# RL78G10_ToF_A2.net
KiCad netlist of a schematic drawn in EAGLE
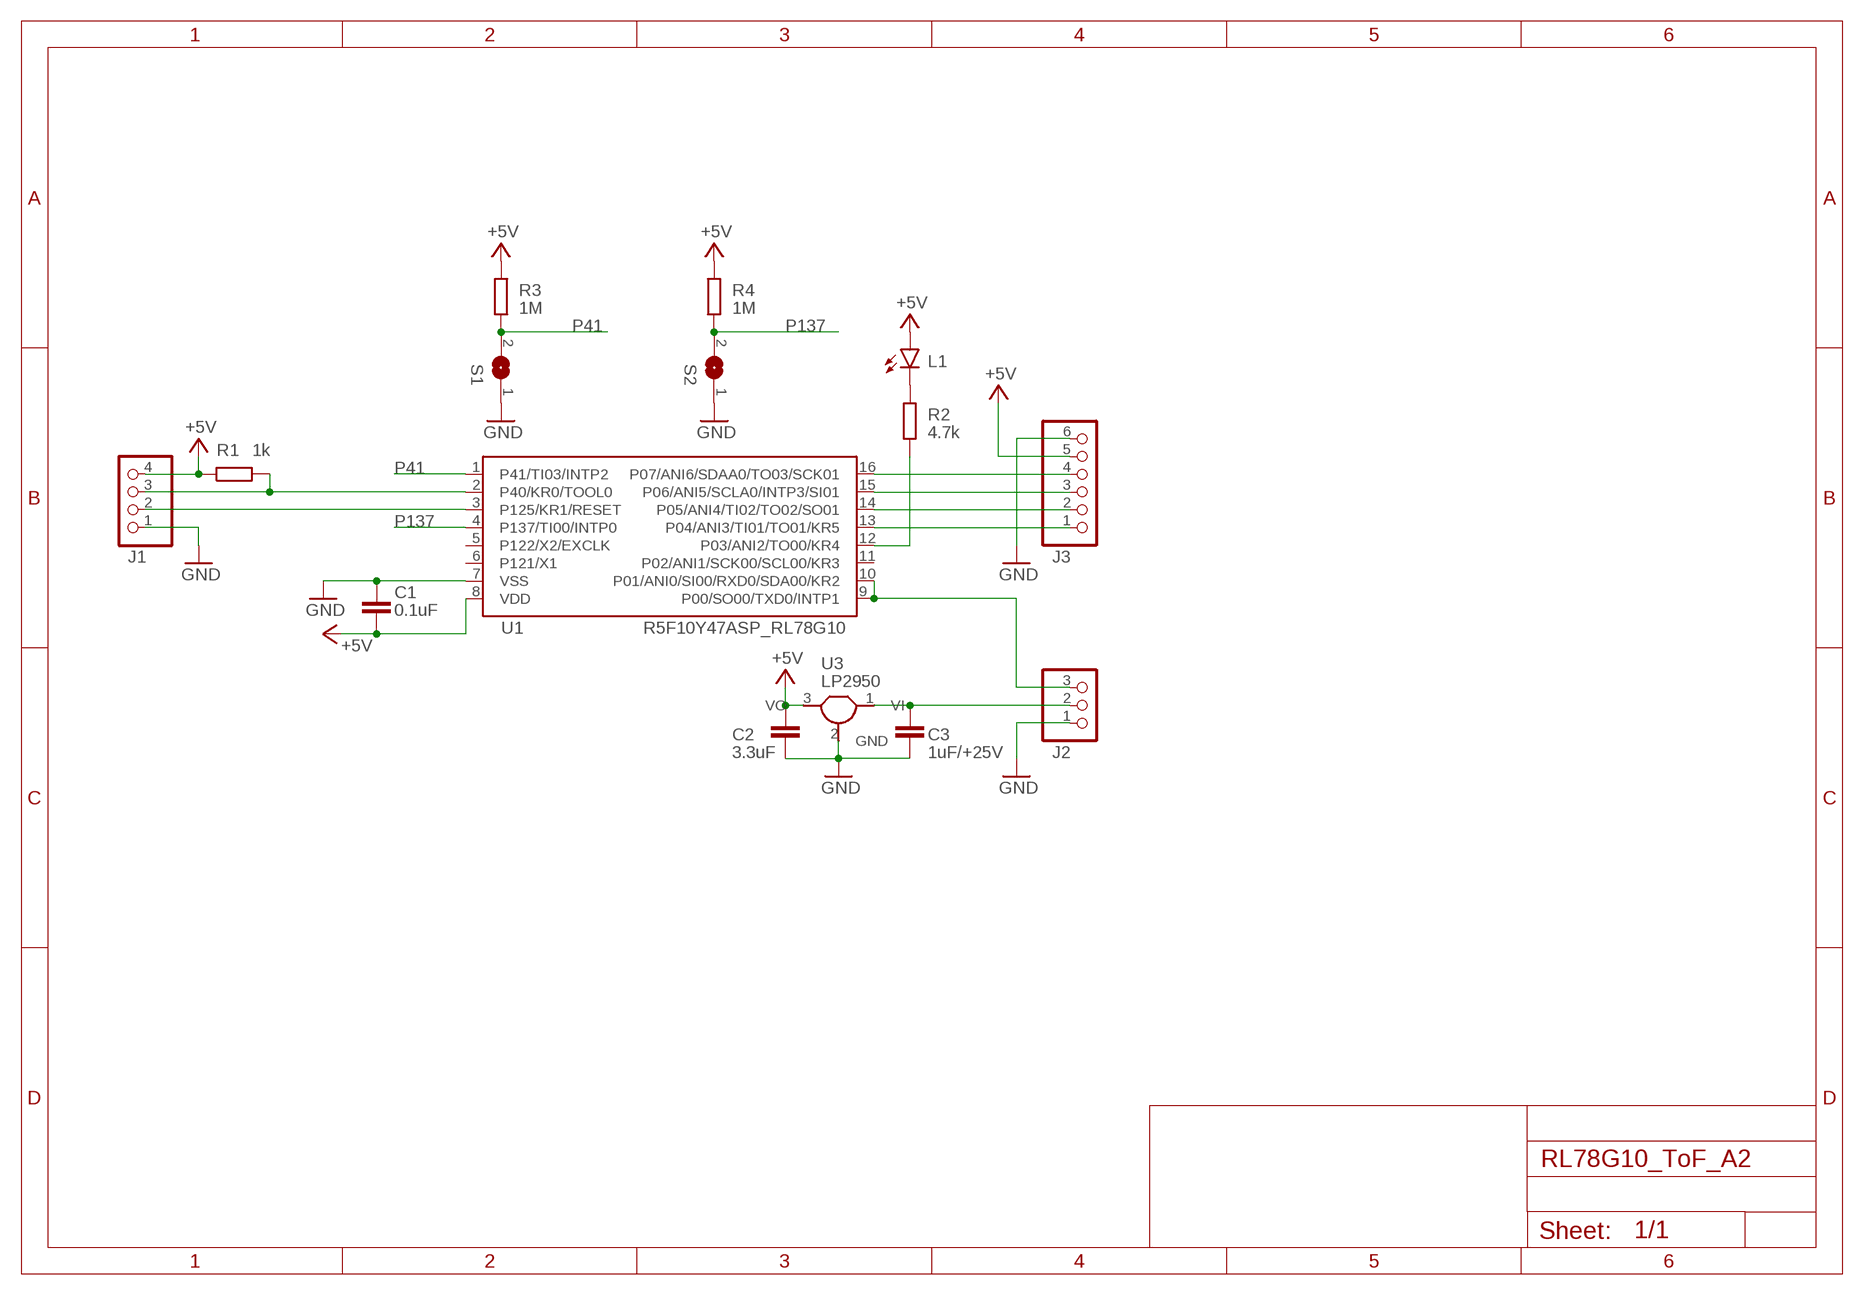
[diagram p0: schematic, sheet 1]

(export (version "E")
  (design (tool "Eeschema 10.0.6"))
  (components
    (comp (ref "C1")
      (value "0.1uF")
      (footprint "eagle-import:C0603")
      (libsource (lib "eagle-import") (part "C-EUC0603"))
    )
    (comp (ref "C2")
      (value "3.3uF")
      (footprint "eagle-import:C0805")
      (libsource (lib "eagle-import") (part "C-EUC0805"))
    )
    (comp (ref "C3")
      (value "1uF/+25V")
      (footprint "eagle-import:C0805")
      (libsource (lib "eagle-import") (part "C-EUC0805"))
    )
    (comp (ref "J1")
      (value "PINHD_1X4")
      (footprint "eagle-import:PINHD_1X04")
      (libsource (lib "eagle-import") (part "PINHD_1X4"))
    )
    (comp (ref "J2")
      (value "PINHD_1X3")
      (footprint "eagle-import:PINHD_1X03")
      (libsource (lib "eagle-import") (part "PINHD_1X3"))
    )
    (comp (ref "J3")
      (value "PINHD_1X6")
      (footprint "eagle-import:PINHD_1X06")
      (libsource (lib "eagle-import") (part "PINHD_1X6"))
    )
    (comp (ref "L1")
      (value "LEDSML0603")
      (footprint "eagle-import:SML0603")
      (libsource (lib "eagle-import") (part "LEDSML0603"))
    )
    (comp (ref "R1")
      (value "1k")
      (footprint "eagle-import:R0603")
      (libsource (lib "eagle-import") (part "R-EU_R0603"))
    )
    (comp (ref "R2")
      (value "4.7k")
      (footprint "eagle-import:R0603")
      (libsource (lib "eagle-import") (part "R-EU_R0603"))
    )
    (comp (ref "R3")
      (value "1M")
      (footprint "eagle-import:R0603")
      (libsource (lib "eagle-import") (part "R-EU_R0603"))
    )
    (comp (ref "R4")
      (value "1M")
      (footprint "eagle-import:R0603")
      (libsource (lib "eagle-import") (part "R-EU_R0603"))
    )
    (comp (ref "S1")
      (value "SJ-OMINI")
      (footprint "eagle-import:SJ-O")
      (libsource (lib "eagle-import") (part "SJ-OMINI"))
    )
    (comp (ref "S2")
      (value "SJ-OMINI")
      (footprint "eagle-import:SJ-O")
      (libsource (lib "eagle-import") (part "SJ-OMINI"))
    )
    (comp (ref "U1")
      (value "R5F10Y47ASP_RL78G10")
      (footprint "eagle-import:SSOP16")
      (libsource (lib "eagle-import") (part "RL78/G10_16"))
    )
    (comp (ref "U3")
      (value "LP2950")
      (footprint "eagle-import:TO92-")
      (libsource (lib "eagle-import") (part "LP2950"))
    )
  )
  (nets
    (net (code "1") (name "+5V") (class "Default")
      (node (ref "C1") (pin "2") (pinfunction "2_2") (pintype "passive"))
      (node (ref "C2") (pin "1") (pinfunction "1_1") (pintype "passive"))
      (node (ref "J1") (pin "4") (pinfunction "4_4") (pintype "passive"))
      (node (ref "J3") (pin "5") (pinfunction "5_5") (pintype "passive"))
      (node (ref "L1") (pin "A") (pinfunction "A_A") (pintype "passive"))
      (node (ref "R1") (pin "1") (pinfunction "1_1") (pintype "passive"))
      (node (ref "R3") (pin "1") (pinfunction "1_1") (pintype "passive"))
      (node (ref "R4") (pin "1") (pinfunction "1_1") (pintype "passive"))
      (node (ref "U1") (pin "8") (pinfunction "VDD_8") (pintype "bidirectional"))
      (node (ref "U3") (pin "3") (pinfunction "VO_3") (pintype "output"))
    )
    (net (code "2") (name "/P41") (class "Default")
      (node (ref "R3") (pin "2") (pinfunction "2_2") (pintype "passive"))
      (node (ref "S1") (pin "2") (pinfunction "2_2") (pintype "passive"))
      (node (ref "U1") (pin "1") (pinfunction "P41/TI03/INTP2_1") (pintype "bidirectional"))
    )
    (net (code "3") (name "/P137") (class "Default")
      (node (ref "R4") (pin "2") (pinfunction "2_2") (pintype "passive"))
      (node (ref "S2") (pin "2") (pinfunction "2_2") (pintype "passive"))
      (node (ref "U1") (pin "4") (pinfunction "P137/TI00/INTP0_4") (pintype "bidirectional"))
    )
    (net (code "4") (name "GND") (class "Default")
      (node (ref "C1") (pin "1") (pinfunction "1_1") (pintype "passive"))
      (node (ref "C2") (pin "2") (pinfunction "2_2") (pintype "passive"))
      (node (ref "C3") (pin "2") (pinfunction "2_2") (pintype "passive"))
      (node (ref "J1") (pin "1") (pinfunction "1_1") (pintype "passive"))
      (node (ref "J2") (pin "1") (pinfunction "1_1") (pintype "passive"))
      (node (ref "J3") (pin "6") (pinfunction "6_6") (pintype "passive"))
      (node (ref "S1") (pin "1") (pinfunction "1_1") (pintype "passive"))
      (node (ref "S2") (pin "1") (pinfunction "1_1") (pintype "passive"))
      (node (ref "U1") (pin "7") (pinfunction "VSS_7") (pintype "bidirectional"))
      (node (ref "U3") (pin "2") (pinfunction "GND_2") (pintype "bidirectional"))
    )
    (net (code "5") (name "Net-(L1-PadC)") (class "Default")
      (node (ref "L1") (pin "C") (pinfunction "C_C") (pintype "passive"))
      (node (ref "R2") (pin "1") (pinfunction "1_1") (pintype "passive"))
    )
    (net (code "6") (name "Net-(U1-P00{slash}SO00{slash}TXD0{slash}INTP1)") (class "Default")
      (node (ref "J2") (pin "3") (pinfunction "3_3") (pintype "passive"))
      (node (ref "U1") (pin "10") (pinfunction "P01/ANI0/SI00/RXD0/SDA00/KR2_10") (pintype "bidirectional"))
      (node (ref "U1") (pin "9") (pinfunction "P00/SO00/TXD0/INTP1_9") (pintype "bidirectional"))
    )
    (net (code "7") (name "Net-(U1-P03{slash}ANI2{slash}TO00{slash}KR4)") (class "Default")
      (node (ref "R2") (pin "2") (pinfunction "2_2") (pintype "passive"))
      (node (ref "U1") (pin "12") (pinfunction "P03/ANI2/TO00/KR4_12") (pintype "bidirectional"))
    )
    (net (code "8") (name "Net-(U1-P04{slash}ANI3{slash}TI01{slash}TO01{slash}KR5)") (class "Default")
      (node (ref "J3") (pin "1") (pinfunction "1_1") (pintype "passive"))
      (node (ref "U1") (pin "13") (pinfunction "P04/ANI3/TI01/TO01/KR5_13") (pintype "bidirectional"))
    )
    (net (code "9") (name "Net-(U1-P05{slash}ANI4{slash}TI02{slash}TO02{slash}SO01)") (class "Default")
      (node (ref "J3") (pin "2") (pinfunction "2_2") (pintype "passive"))
      (node (ref "U1") (pin "14") (pinfunction "P05/ANI4/TI02/TO02/SO01_14") (pintype "bidirectional"))
    )
    (net (code "10") (name "Net-(U1-P06{slash}ANI5{slash}SCLA0{slash}INTP3{slash}SI01)") (class "Default")
      (node (ref "J3") (pin "3") (pinfunction "3_3") (pintype "passive"))
      (node (ref "U1") (pin "15") (pinfunction "P06/ANI5/SCLA0/INTP3/SI01_15") (pintype "bidirectional"))
    )
    (net (code "11") (name "Net-(U1-P07{slash}ANI6{slash}SDAA0{slash}TO03{slash}SCK01)") (class "Default")
      (node (ref "J3") (pin "4") (pinfunction "4_4") (pintype "passive"))
      (node (ref "U1") (pin "16") (pinfunction "P07/ANI6/SDAA0/TO03/SCK01_16") (pintype "bidirectional"))
    )
    (net (code "12") (name "Net-(U1-P40{slash}KR0{slash}TOOL0)") (class "Default")
      (node (ref "J1") (pin "3") (pinfunction "3_3") (pintype "passive"))
      (node (ref "R1") (pin "2") (pinfunction "2_2") (pintype "passive"))
      (node (ref "U1") (pin "2") (pinfunction "P40/KR0/TOOL0_2") (pintype "bidirectional"))
    )
    (net (code "13") (name "Net-(U1-P125{slash}KR1{slash}RESET)") (class "Default")
      (node (ref "J1") (pin "2") (pinfunction "2_2") (pintype "passive"))
      (node (ref "U1") (pin "3") (pinfunction "P125/KR1/RESET_3") (pintype "bidirectional"))
    )
    (net (code "14") (name "Net-(U3-VI)") (class "Default")
      (node (ref "C3") (pin "1") (pinfunction "1_1") (pintype "passive"))
      (node (ref "J2") (pin "2") (pinfunction "2_2") (pintype "passive"))
      (node (ref "U3") (pin "1") (pinfunction "VI_1") (pintype "input"))
    )
    (net (code "15") (name "unconnected-(U1-P02{slash}ANI1{slash}SCK00{slash}SCL00{slash}KR3-Pad11)") (class "Default")
      (node (ref "U1") (pin "11") (pinfunction "P02/ANI1/SCK00/SCL00/KR3_11") (pintype "bidirectional"))
    )
    (net (code "16") (name "unconnected-(U1-P121{slash}X1-Pad6)") (class "Default")
      (node (ref "U1") (pin "6") (pinfunction "P121/X1_6") (pintype "bidirectional"))
    )
    (net (code "17") (name "unconnected-(U1-P122{slash}X2{slash}EXCLK-Pad5)") (class "Default")
      (node (ref "U1") (pin "5") (pinfunction "P122/X2/EXCLK_5") (pintype "bidirectional"))
    )
  )
)
